# Crazebird-v0_8.net
KiCad netlist of a schematic drawn in EAGLE
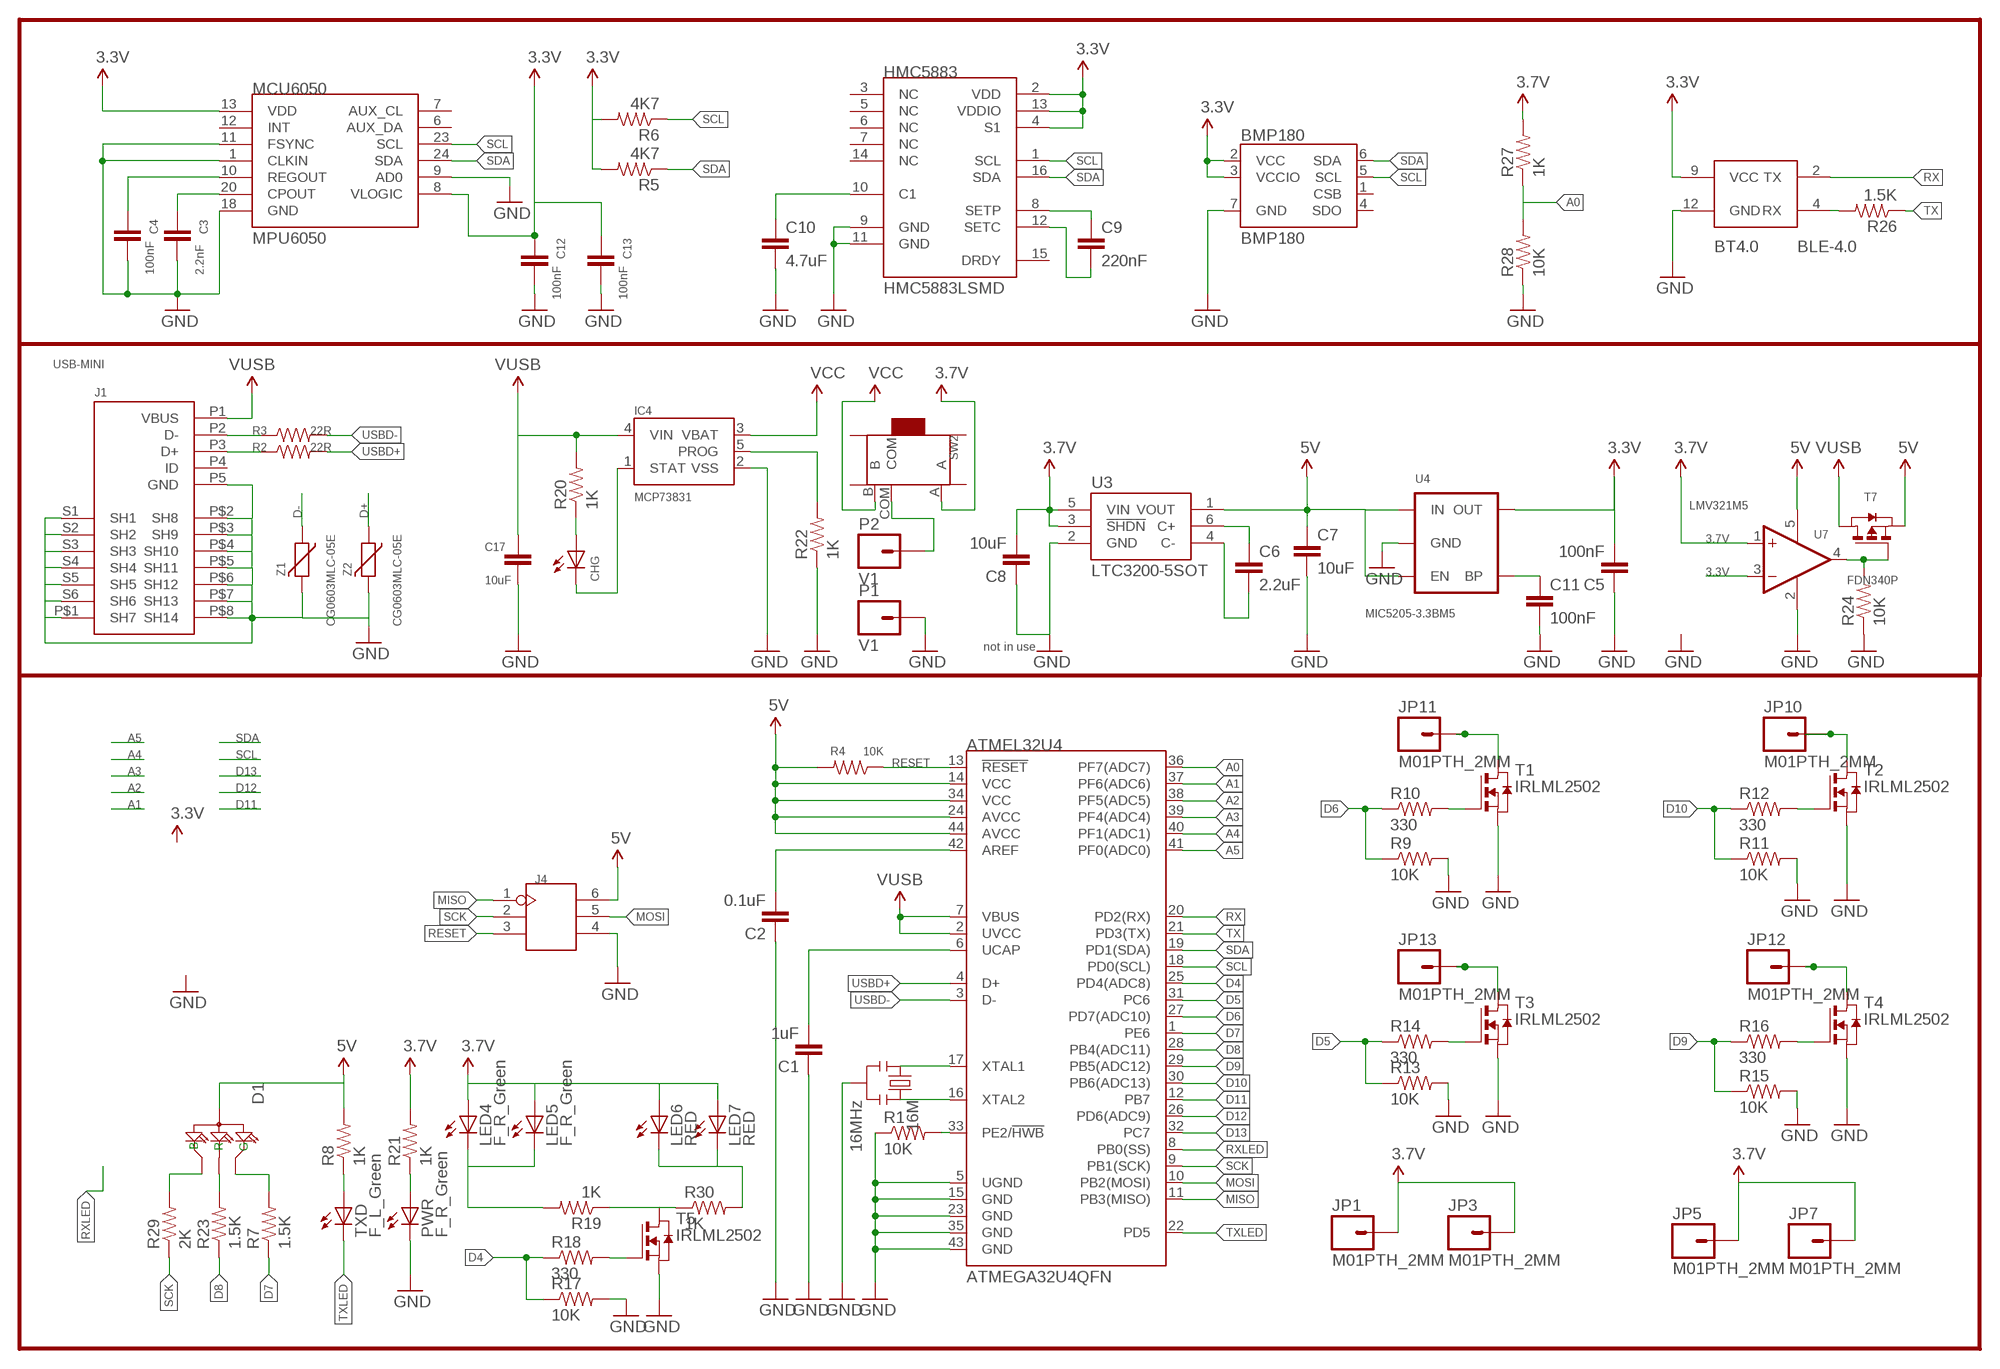
[diagram p0: schematic, sheet 1]

(export (version "E")
  (design (tool "Eeschema 10.0.6"))
  (components
    (comp (ref "16M")
      (value "16MHz")
      (footprint "eagle-import:RESONATOR-SMD")
      (libsource (lib "eagle-import") (part "RESONATOR16MHZ"))
    )
    (comp (ref "ATMEL32U4")
      (value "ATMEGA32U4QFN")
      (footprint "eagle-import:SPARKFUN-DIGITALIC_QFN-44")
      (libsource (lib "eagle-import") (part "ATMEGA32U4QFN"))
    )
    (comp (ref "BMP180")
      (value "BMP180")
      (footprint "eagle-import:BMP180")
      (libsource (lib "eagle-import") (part "BMP180"))
    )
    (comp (ref "BT4.0")
      (value "BLE-4.0")
      (footprint "eagle-import:HEXAIRBOT-HEXNANO_BLUETOOTH_HM11")
      (libsource (lib "eagle-import") (part "HEXAIRBOT-HEXNANO_BLUETOOTH_HM11"))
    )
    (comp (ref "C1")
      (value "1uF")
      (footprint "eagle-import:0402-CAP")
      (libsource (lib "eagle-import") (part "SparkFun-Passives_CAP0402-CAP"))
    )
    (comp (ref "C2")
      (value "0.1uF")
      (footprint "eagle-import:0402-CAP")
      (libsource (lib "eagle-import") (part "SparkFun-Passives_CAP0402-CAP"))
    )
    (comp (ref "C3")
      (value "2.2nF")
      (footprint "eagle-import:0402-CAP")
      (libsource (lib "eagle-import") (part "SparkFun-Passives_CAP0402-CAP"))
    )
    (comp (ref "C4")
      (value "100nF")
      (footprint "eagle-import:0402-CAP")
      (libsource (lib "eagle-import") (part "SparkFun-Passives_CAP0402-CAP"))
    )
    (comp (ref "C5")
      (value "100nF")
      (footprint "eagle-import:0402-CAP")
      (libsource (lib "eagle-import") (part "SparkFun-Passives_CAP0402-CAP"))
    )
    (comp (ref "C6")
      (value "2.2uF")
      (footprint "eagle-import:0402-CAP")
      (libsource (lib "eagle-import") (part "SparkFun-Passives_CAP0402-CAP"))
    )
    (comp (ref "C7")
      (value "10uF")
      (footprint "eagle-import:0402-CAP")
      (libsource (lib "eagle-import") (part "SparkFun-Passives_CAP0402-CAP"))
    )
    (comp (ref "C8")
      (value "10uF")
      (footprint "eagle-import:0805")
      (libsource (lib "eagle-import") (part "SparkFun-Passives_CAP0805"))
    )
    (comp (ref "C9")
      (value "220nF")
      (footprint "eagle-import:0402-CAP")
      (libsource (lib "eagle-import") (part "SparkFun-Passives_CAP0402-CAP"))
    )
    (comp (ref "C10")
      (value "4.7uF")
      (footprint "eagle-import:0402-CAP")
      (libsource (lib "eagle-import") (part "SparkFun-Passives_CAP0402-CAP"))
    )
    (comp (ref "C11")
      (value "100nF")
      (footprint "eagle-import:0402-CAP")
      (libsource (lib "eagle-import") (part "SparkFun-Passives_CAP0402-CAP"))
    )
    (comp (ref "C12")
      (value "100nF")
      (footprint "eagle-import:0402-CAP")
      (libsource (lib "eagle-import") (part "SparkFun-Passives_CAP0402-CAP"))
    )
    (comp (ref "C13")
      (value "100nF")
      (footprint "eagle-import:0402-CAP")
      (libsource (lib "eagle-import") (part "SparkFun-Passives_CAP0402-CAP"))
    )
    (comp (ref "C17")
      (value "10uF")
      (footprint "eagle-import:0805")
      (libsource (lib "eagle-import") (part "CAP0805"))
    )
    (comp (ref "CHG")
      (value "Yellow")
      (footprint "eagle-import:CHIPLED_0603")
      (libsource (lib "eagle-import") (part "LEDCHIPLED_0603"))
    )
    (comp (ref "D1")
      (value "LED-ARGB-4P-1206")
      (footprint "eagle-import:LED-4P-1206-3.0X1.5")
      (libsource (lib "eagle-import") (part "LED-ARGB-4P-1206"))
    )
    (comp (ref "HMC5883")
      (value "HMC5883LSMD")
      (footprint "eagle-import:16LPCC")
      (libsource (lib "eagle-import") (part "HMC5883LSMD"))
    )
    (comp (ref "IC4")
      (value "MCP73831")
      (footprint "eagle-import:SOT23-5")
      (libsource (lib "eagle-import") (part "MCP73831"))
    )
    (comp (ref "J1")
      (value "USB-MINI")
      (footprint "eagle-import:USB_MICRO")
      (libsource (lib "eagle-import") (part "USB-MINI"))
    )
    (comp (ref "J4")
      (value "CONNECTOR_HEADER-2X3P-2.0")
      (footprint "eagle-import:CONNECTOR_2X3P-2.0")
      (libsource (lib "eagle-import") (part "CONNECTOR_HEADER-2X3P-2.0"))
    )
    (comp (ref "JP1")
      (value "M01PTH_2MM")
      (footprint "eagle-import:1X01_2MM")
      (libsource (lib "eagle-import") (part "duinofun-connector_M01PTH_2MM"))
    )
    (comp (ref "JP3")
      (value "M01PTH_2MM")
      (footprint "eagle-import:1X01_2MM")
      (libsource (lib "eagle-import") (part "duinofun-connector_M01PTH_2MM"))
    )
    (comp (ref "JP5")
      (value "M01PTH_2MM")
      (footprint "eagle-import:1X01_2MM")
      (libsource (lib "eagle-import") (part "duinofun-connector_M01PTH_2MM"))
    )
    (comp (ref "JP7")
      (value "M01PTH_2MM")
      (footprint "eagle-import:1X01_2MM")
      (libsource (lib "eagle-import") (part "duinofun-connector_M01PTH_2MM"))
    )
    (comp (ref "JP10")
      (value "M01PTH_2MM")
      (footprint "eagle-import:1X01_2MM")
      (libsource (lib "eagle-import") (part "duinofun-connector_M01PTH_2MM"))
    )
    (comp (ref "JP11")
      (value "M01PTH_2MM")
      (footprint "eagle-import:1X01_2MM")
      (libsource (lib "eagle-import") (part "duinofun-connector_M01PTH_2MM"))
    )
    (comp (ref "JP12")
      (value "M01PTH_2MM")
      (footprint "eagle-import:1X01_2MM")
      (libsource (lib "eagle-import") (part "duinofun-connector_M01PTH_2MM"))
    )
    (comp (ref "JP13")
      (value "M01PTH_2MM")
      (footprint "eagle-import:1X01_2MM")
      (libsource (lib "eagle-import") (part "duinofun-connector_M01PTH_2MM"))
    )
    (comp (ref "LED4")
      (value "F_R_Green")
      (footprint "eagle-import:CHIPLED_0603")
      (libsource (lib "eagle-import") (part "LEDCHIPLED_0603"))
    )
    (comp (ref "LED5")
      (value "F_R_Green")
      (footprint "eagle-import:CHIPLED_0603")
      (libsource (lib "eagle-import") (part "LEDCHIPLED_0603"))
    )
    (comp (ref "LED6")
      (value "RED")
      (footprint "eagle-import:CHIPLED_0603")
      (libsource (lib "eagle-import") (part "LEDCHIPLED_0603"))
    )
    (comp (ref "LED7")
      (value "RED")
      (footprint "eagle-import:CHIPLED_0603")
      (libsource (lib "eagle-import") (part "LEDCHIPLED_0603"))
    )
    (comp (ref "MCU6050")
      (value "MPU6050")
      (footprint "eagle-import:TESTING_QFN-24-4MM2")
      (libsource (lib "eagle-import") (part "TESTING_MPU-6050-1"))
    )
    (comp (ref "P1")
      (value "V1")
      (footprint "eagle-import:1X01")
      (libsource (lib "eagle-import") (part "M01PTH"))
    )
    (comp (ref "P2")
      (value "V1")
      (footprint "eagle-import:1X01")
      (libsource (lib "eagle-import") (part "M01PTH"))
    )
    (comp (ref "PWR")
      (value "F_R_Green")
      (footprint "eagle-import:CHIPLED_0603")
      (libsource (lib "eagle-import") (part "LEDCHIPLED_0603"))
    )
    (comp (ref "R1")
      (value "10K")
      (footprint "eagle-import:0402-RES")
      (libsource (lib "eagle-import") (part "RESISTOR0402-RES"))
    )
    (comp (ref "R2")
      (value "22R")
      (footprint "eagle-import:0402-RES")
      (libsource (lib "eagle-import") (part "RESISTOR0402-RES"))
    )
    (comp (ref "R3")
      (value "22R")
      (footprint "eagle-import:0402-RES")
      (libsource (lib "eagle-import") (part "RESISTOR0402-RES"))
    )
    (comp (ref "R4")
      (value "10K")
      (footprint "eagle-import:0402-RES")
      (libsource (lib "eagle-import") (part "RESISTOR0402-RES"))
    )
    (comp (ref "R5")
      (value "4K7")
      (footprint "eagle-import:0402-RES")
      (libsource (lib "eagle-import") (part "RESISTOR0402-RES"))
    )
    (comp (ref "R6")
      (value "4K7")
      (footprint "eagle-import:0402-RES")
      (libsource (lib "eagle-import") (part "RESISTOR0402-RES"))
    )
    (comp (ref "R7")
      (value "1.5K")
      (footprint "eagle-import:0402-RES")
      (libsource (lib "eagle-import") (part "RESISTOR0402-RES"))
    )
    (comp (ref "R8")
      (value "1K")
      (footprint "eagle-import:0402-RES")
      (libsource (lib "eagle-import") (part "RESISTOR0402-RES"))
    )
    (comp (ref "R9")
      (value "10K")
      (footprint "eagle-import:0402-RES")
      (libsource (lib "eagle-import") (part "RESISTOR0402-RES"))
    )
    (comp (ref "R10")
      (value "330")
      (footprint "eagle-import:0402-RES")
      (libsource (lib "eagle-import") (part "RESISTOR0402-RES"))
    )
    (comp (ref "R11")
      (value "10K")
      (footprint "eagle-import:0402-RES")
      (libsource (lib "eagle-import") (part "RESISTOR0402-RES"))
    )
    (comp (ref "R12")
      (value "330")
      (footprint "eagle-import:0402-RES")
      (libsource (lib "eagle-import") (part "RESISTOR0402-RES"))
    )
    (comp (ref "R13")
      (value "10K")
      (footprint "eagle-import:0402-RES")
      (libsource (lib "eagle-import") (part "RESISTOR0402-RES"))
    )
    (comp (ref "R14")
      (value "330")
      (footprint "eagle-import:0402-RES")
      (libsource (lib "eagle-import") (part "RESISTOR0402-RES"))
    )
    (comp (ref "R15")
      (value "10K")
      (footprint "eagle-import:0402-RES")
      (libsource (lib "eagle-import") (part "RESISTOR0402-RES"))
    )
    (comp (ref "R16")
      (value "330")
      (footprint "eagle-import:0402-RES")
      (libsource (lib "eagle-import") (part "RESISTOR0402-RES"))
    )
    (comp (ref "R17")
      (value "10K")
      (footprint "eagle-import:0402-RES")
      (libsource (lib "eagle-import") (part "RESISTOR0402-RES"))
    )
    (comp (ref "R18")
      (value "330")
      (footprint "eagle-import:0402-RES")
      (libsource (lib "eagle-import") (part "RESISTOR0402-RES"))
    )
    (comp (ref "R19")
      (value "1K")
      (footprint "eagle-import:0402-RES")
      (libsource (lib "eagle-import") (part "RESISTOR0402-RES"))
    )
    (comp (ref "R20")
      (value "1K")
      (footprint "eagle-import:0402-RES")
      (libsource (lib "eagle-import") (part "RESISTOR0402-RES"))
    )
    (comp (ref "R21")
      (value "1K")
      (footprint "eagle-import:0402-RES")
      (libsource (lib "eagle-import") (part "RESISTOR0402-RES"))
    )
    (comp (ref "R22")
      (value "1K")
      (footprint "eagle-import:0402-RES")
      (libsource (lib "eagle-import") (part "RESISTOR0402-RES"))
    )
    (comp (ref "R23")
      (value "1.5K")
      (footprint "eagle-import:0402-RES")
      (libsource (lib "eagle-import") (part "RESISTOR0402-RES"))
    )
    (comp (ref "R24")
      (value "10K")
      (footprint "eagle-import:0402-RES")
      (libsource (lib "eagle-import") (part "RESISTOR0402-RES"))
    )
    (comp (ref "R26")
      (value "1.5K")
      (footprint "eagle-import:0402-RES")
      (libsource (lib "eagle-import") (part "RESISTOR0402-RES"))
    )
    (comp (ref "R27")
      (value "1K")
      (footprint "eagle-import:0402-RES")
      (libsource (lib "eagle-import") (part "RESISTOR0402-RES"))
    )
    (comp (ref "R28")
      (value "10K")
      (footprint "eagle-import:0402-RES")
      (libsource (lib "eagle-import") (part "RESISTOR0402-RES"))
    )
    (comp (ref "R29")
      (value "2K")
      (footprint "eagle-import:0402-RES")
      (libsource (lib "eagle-import") (part "RESISTOR0402-RES"))
    )
    (comp (ref "R30")
      (value "1K")
      (footprint "eagle-import:0402-RES")
      (libsource (lib "eagle-import") (part "RESISTOR0402-RES"))
    )
    (comp (ref "SW2")
      (value "SWITCH-3P-SMD-6.6X2.8")
      (footprint "eagle-import:3P-SMD-2CH-6.6X2.8-REINFORCE")
      (libsource (lib "eagle-import") (part "SWITCH-3P-SMD-6.6X2.8"))
    )
    (comp (ref "T1")
      (value "IRLML2502")
      (footprint "eagle-import:SOT-23")
      (libsource (lib "eagle-import") (part "NMOSSOT23"))
    )
    (comp (ref "T2")
      (value "IRLML2502")
      (footprint "eagle-import:SOT-23")
      (libsource (lib "eagle-import") (part "NMOSSOT23"))
    )
    (comp (ref "T3")
      (value "IRLML2502")
      (footprint "eagle-import:SOT-23")
      (libsource (lib "eagle-import") (part "NMOSSOT23"))
    )
    (comp (ref "T4")
      (value "IRLML2502")
      (footprint "eagle-import:SOT-23")
      (libsource (lib "eagle-import") (part "NMOSSOT23"))
    )
    (comp (ref "T5")
      (value "IRLML2502")
      (footprint "eagle-import:SOT-23")
      (libsource (lib "eagle-import") (part "NMOSSOT23"))
    )
    (comp (ref "T7")
      (value "FDN340P")
      (footprint "eagle-import:SOT23")
      (libsource (lib "eagle-import") (part "FDN340P"))
    )
    (comp (ref "TXD")
      (value "F_L_Green")
      (footprint "eagle-import:CHIPLED_0603")
      (libsource (lib "eagle-import") (part "LEDCHIPLED_0603"))
    )
    (comp (ref "U3")
      (value "LTC3200-5SOT")
      (footprint "eagle-import:SOT23-6")
      (libsource (lib "eagle-import") (part "LTC3200-5SOT"))
    )
    (comp (ref "U4")
      (value "MIC5205-3.3BM5")
      (footprint "eagle-import:SOT23-5")
      (libsource (lib "eagle-import") (part "MIC52053.3V"))
    )
    (comp (ref "U7")
      (value "LMV321M5")
      (footprint "eagle-import:SOT23-5")
      (libsource (lib "eagle-import") (part "LMV321?M5"))
    )
    (comp (ref "Z1")
      (value "CG0603MLC-05E")
      (footprint "eagle-import:CT_CN0603")
      (libsource (lib "eagle-import") (part "VARISTORCN0603"))
    )
    (comp (ref "Z2")
      (value "CG0603MLC-05E")
      (footprint "eagle-import:CT_CN0603")
      (libsource (lib "eagle-import") (part "VARISTORCN0603"))
    )
  )
  (nets
    (net (code "1") (name "/D+") (class "Default")
      (node (ref "J1") (pin "P3") (pinfunction "D+_P3") (pintype "bidirectional"))
      (node (ref "R2") (pin "1") (pinfunction "1_1") (pintype "passive"))
      (node (ref "Z2") (pin "1") (pinfunction "1_1") (pintype "passive"))
    )
    (net (code "2") (name "/D-") (class "Default")
      (node (ref "J1") (pin "P2") (pinfunction "D-_P2") (pintype "bidirectional"))
      (node (ref "R3") (pin "1") (pinfunction "1_1") (pintype "passive"))
      (node (ref "Z1") (pin "1") (pinfunction "1_1") (pintype "passive"))
    )
    (net (code "3") (name "3.3V") (class "Default")
      (node (ref "BMP180") (pin "2") (pinfunction "VCC_2") (pintype "power_in"))
      (node (ref "BMP180") (pin "3") (pinfunction "VCCIO_3") (pintype "power_in"))
      (node (ref "BT4.0") (pin "9") (pinfunction "VCC_9") (pintype "bidirectional"))
      (node (ref "C12") (pin "1") (pinfunction "1_1") (pintype "passive"))
      (node (ref "C13") (pin "1") (pinfunction "1_1") (pintype "passive"))
      (node (ref "C5") (pin "2") (pinfunction "2_2") (pintype "passive"))
      (node (ref "HMC5883") (pin "13") (pinfunction "VDDIO_13") (pintype "bidirectional"))
      (node (ref "HMC5883") (pin "2") (pinfunction "VDD_2") (pintype "bidirectional"))
      (node (ref "HMC5883") (pin "4") (pinfunction "S1_4") (pintype "bidirectional"))
      (node (ref "MCU6050") (pin "13") (pinfunction "VDD_13") (pintype "bidirectional"))
      (node (ref "MCU6050") (pin "8") (pinfunction "VLOGIC_8") (pintype "bidirectional"))
      (node (ref "R5") (pin "2") (pinfunction "2_2") (pintype "passive"))
      (node (ref "R6") (pin "2") (pinfunction "2_2") (pintype "passive"))
      (node (ref "U4") (pin "5") (pinfunction "OUT_5") (pintype "passive"))
      (node (ref "U7") (pin "3") (pinfunction "-IN_3") (pintype "input"))
    )
    (net (code "4") (name "3.7V") (class "Default")
      (node (ref "C8") (pin "2") (pinfunction "2_2") (pintype "passive"))
      (node (ref "JP1") (pin "1") (pinfunction "1_1") (pintype "passive"))
      (node (ref "JP3") (pin "1") (pinfunction "1_1") (pintype "passive"))
      (node (ref "JP5") (pin "1") (pinfunction "1_1") (pintype "passive"))
      (node (ref "JP7") (pin "1") (pinfunction "1_1") (pintype "passive"))
      (node (ref "LED4") (pin "A") (pinfunction "A_A") (pintype "passive"))
      (node (ref "LED5") (pin "A") (pinfunction "A_A") (pintype "passive"))
      (node (ref "LED6") (pin "A") (pinfunction "A_A") (pintype "passive"))
      (node (ref "LED7") (pin "A") (pinfunction "A_A") (pintype "passive"))
      (node (ref "R21") (pin "2") (pinfunction "2_2") (pintype "passive"))
      (node (ref "R27") (pin "2") (pinfunction "2_2") (pintype "passive"))
      (node (ref "SW2") (pin "A") (pinfunction "A_A") (pintype "bidirectional"))
      (node (ref "U3") (pin "3") (pinfunction "~{SHDN}_3") (pintype "bidirectional"))
      (node (ref "U3") (pin "5") (pinfunction "VIN_5") (pintype "bidirectional"))
      (node (ref "U7") (pin "1") (pinfunction "+IN_1") (pintype "input"))
    )
    (net (code "5") (name "5V") (class "Default")
      (node (ref "ATMEL32U4") (pin "14") (pinfunction "VCC_14") (pintype "bidirectional"))
      (node (ref "ATMEL32U4") (pin "24") (pinfunction "AVCC_24") (pintype "bidirectional"))
      (node (ref "ATMEL32U4") (pin "34") (pinfunction "VCC_34") (pintype "bidirectional"))
      (node (ref "ATMEL32U4") (pin "44") (pinfunction "AVCC_44") (pintype "bidirectional"))
      (node (ref "C7") (pin "1") (pinfunction "1_1") (pintype "passive"))
      (node (ref "D1") (pin "2") (pinfunction "+_2") (pintype "bidirectional"))
      (node (ref "J4") (pin "6") (pinfunction "6_6") (pintype "bidirectional"))
      (node (ref "R4") (pin "2") (pinfunction "2_2") (pintype "passive"))
      (node (ref "R8") (pin "2") (pinfunction "2_2") (pintype "passive"))
      (node (ref "T7") (pin "2") (pinfunction "S_2") (pintype "passive"))
      (node (ref "U3") (pin "1") (pinfunction "VOUT_1") (pintype "bidirectional"))
      (node (ref "U4") (pin "1") (pinfunction "IN_1") (pintype "input"))
      (node (ref "U4") (pin "3") (pinfunction "EN_3") (pintype "input"))
      (node (ref "U7") (pin "5") (pinfunction "V+_5") (pintype "power_in"))
    )
    (net (code "6") (name "A0") (class "Default")
      (node (ref "ATMEL32U4") (pin "36") (pinfunction "PF7(ADC7)_36") (pintype "bidirectional"))
      (node (ref "R27") (pin "1") (pinfunction "1_1") (pintype "passive"))
      (node (ref "R28") (pin "2") (pinfunction "2_2") (pintype "passive"))
    )
    (net (code "7") (name "A1") (class "Default")
      (node (ref "ATMEL32U4") (pin "37") (pinfunction "PF6(ADC6)_37") (pintype "bidirectional"))
    )
    (net (code "8") (name "A2") (class "Default")
      (node (ref "ATMEL32U4") (pin "38") (pinfunction "PF5(ADC5)_38") (pintype "bidirectional"))
    )
    (net (code "9") (name "A3") (class "Default")
      (node (ref "ATMEL32U4") (pin "39") (pinfunction "PF4(ADC4)_39") (pintype "bidirectional"))
    )
    (net (code "10") (name "A4") (class "Default")
      (node (ref "ATMEL32U4") (pin "40") (pinfunction "PF1(ADC1)_40") (pintype "bidirectional"))
    )
    (net (code "11") (name "A5") (class "Default")
      (node (ref "ATMEL32U4") (pin "41") (pinfunction "PF0(ADC0)_41") (pintype "bidirectional"))
    )
    (net (code "12") (name "D4") (class "Default")
      (node (ref "ATMEL32U4") (pin "25") (pinfunction "PD4(ADC8)_25") (pintype "bidirectional"))
      (node (ref "R17") (pin "1") (pinfunction "1_1") (pintype "passive"))
      (node (ref "R18") (pin "1") (pinfunction "1_1") (pintype "passive"))
    )
    (net (code "13") (name "D5") (class "Default")
      (node (ref "ATMEL32U4") (pin "31") (pinfunction "PC6_31") (pintype "bidirectional"))
      (node (ref "R13") (pin "1") (pinfunction "1_1") (pintype "passive"))
      (node (ref "R14") (pin "1") (pinfunction "1_1") (pintype "passive"))
    )
    (net (code "14") (name "D6") (class "Default")
      (node (ref "ATMEL32U4") (pin "27") (pinfunction "PD7(ADC10)_27") (pintype "bidirectional"))
      (node (ref "R10") (pin "1") (pinfunction "1_1") (pintype "passive"))
      (node (ref "R9") (pin "1") (pinfunction "1_1") (pintype "passive"))
    )
    (net (code "15") (name "D7") (class "Default")
      (node (ref "ATMEL32U4") (pin "1") (pinfunction "PE6_1") (pintype "bidirectional"))
      (node (ref "R7") (pin "1") (pinfunction "1_1") (pintype "passive"))
    )
    (net (code "16") (name "D8") (class "Default")
      (node (ref "ATMEL32U4") (pin "28") (pinfunction "PB4(ADC11)_28") (pintype "bidirectional"))
      (node (ref "R23") (pin "1") (pinfunction "1_1") (pintype "passive"))
    )
    (net (code "17") (name "D9") (class "Default")
      (node (ref "ATMEL32U4") (pin "29") (pinfunction "PB5(ADC12)_29") (pintype "bidirectional"))
      (node (ref "R15") (pin "1") (pinfunction "1_1") (pintype "passive"))
      (node (ref "R16") (pin "1") (pinfunction "1_1") (pintype "passive"))
    )
    (net (code "18") (name "D10") (class "Default")
      (node (ref "ATMEL32U4") (pin "30") (pinfunction "PB6(ADC13)_30") (pintype "bidirectional"))
      (node (ref "R11") (pin "1") (pinfunction "1_1") (pintype "passive"))
      (node (ref "R12") (pin "1") (pinfunction "1_1") (pintype "passive"))
    )
    (net (code "19") (name "D11") (class "Default")
      (node (ref "ATMEL32U4") (pin "12") (pinfunction "PB7_12") (pintype "bidirectional"))
    )
    (net (code "20") (name "D12") (class "Default")
      (node (ref "ATMEL32U4") (pin "26") (pinfunction "PD6(ADC9)_26") (pintype "bidirectional"))
    )
    (net (code "21") (name "D13") (class "Default")
      (node (ref "ATMEL32U4") (pin "32") (pinfunction "PC7_32") (pintype "bidirectional"))
    )
    (net (code "22") (name "GND") (class "Default")
      (node (ref "16M") (pin "2") (pinfunction "2_2") (pintype "passive"))
      (node (ref "ATMEL32U4") (pin "15") (pinfunction "GND_15") (pintype "bidirectional"))
      (node (ref "ATMEL32U4") (pin "23") (pinfunction "GND_23") (pintype "bidirectional"))
      (node (ref "ATMEL32U4") (pin "35") (pinfunction "GND_35") (pintype "bidirectional"))
      (node (ref "ATMEL32U4") (pin "43") (pinfunction "GND_43") (pintype "bidirectional"))
      (node (ref "ATMEL32U4") (pin "5") (pinfunction "UGND_5") (pintype "bidirectional"))
      (node (ref "BMP180") (pin "7") (pinfunction "GND_7") (pintype "power_in"))
      (node (ref "BT4.0") (pin "12") (pinfunction "GND_12") (pintype "bidirectional"))
      (node (ref "C1") (pin "1") (pinfunction "1_1") (pintype "passive"))
      (node (ref "C10") (pin "2") (pinfunction "2_2") (pintype "passive"))
      (node (ref "C11") (pin "2") (pinfunction "2_2") (pintype "passive"))
      (node (ref "C12") (pin "2") (pinfunction "2_2") (pintype "passive"))
      (node (ref "C13") (pin "2") (pinfunction "2_2") (pintype "passive"))
      (node (ref "C17") (pin "1") (pinfunction "1_1") (pintype "passive"))
      (node (ref "C2") (pin "1") (pinfunction "1_1") (pintype "passive"))
      (node (ref "C3") (pin "2") (pinfunction "2_2") (pintype "passive"))
      (node (ref "C4") (pin "2") (pinfunction "2_2") (pintype "passive"))
      (node (ref "C5") (pin "1") (pinfunction "1_1") (pintype "passive"))
      (node (ref "C7") (pin "2") (pinfunction "2_2") (pintype "passive"))
      (node (ref "C8") (pin "1") (pinfunction "1_1") (pintype "passive"))
      (node (ref "HMC5883") (pin "11") (pinfunction "GND_11") (pintype "bidirectional"))
      (node (ref "HMC5883") (pin "9") (pinfunction "GND_9") (pintype "bidirectional"))
      (node (ref "IC4") (pin "2") (pinfunction "VSS_2") (pintype "power_in"))
      (node (ref "J1") (pin "P$1") (pinfunction "SH7_P$1") (pintype "passive"))
      (node (ref "J1") (pin "P$2") (pinfunction "SH8_P$2") (pintype "passive"))
      (node (ref "J1") (pin "P$3") (pinfunction "SH9_P$3") (pintype "passive"))
      (node (ref "J1") (pin "P$4") (pinfunction "SH10_P$4") (pintype "passive"))
      (node (ref "J1") (pin "P$5") (pinfunction "SH11_P$5") (pintype "passive"))
      (node (ref "J1") (pin "P$6") (pinfunction "SH12_P$6") (pintype "passive"))
      (node (ref "J1") (pin "P$7") (pinfunction "SH13_P$7") (pintype "passive"))
      (node (ref "J1") (pin "P$8") (pinfunction "SH14_P$8") (pintype "passive"))
      (node (ref "J1") (pin "P5") (pinfunction "GND_P5") (pintype "passive"))
      (node (ref "J1") (pin "S1") (pinfunction "SH1_S1") (pintype "passive"))
      (node (ref "J1") (pin "S2") (pinfunction "SH2_S2") (pintype "passive"))
      (node (ref "J1") (pin "S3") (pinfunction "SH3_S3") (pintype "passive"))
      (node (ref "J1") (pin "S4") (pinfunction "SH4_S4") (pintype "passive"))
      (node (ref "J1") (pin "S5") (pinfunction "SH5_S5") (pintype "passive"))
      (node (ref "J1") (pin "S6") (pinfunction "SH6_S6") (pintype "passive"))
      (node (ref "J4") (pin "4") (pinfunction "4_4") (pintype "bidirectional"))
      (node (ref "MCU6050") (pin "1") (pinfunction "CLKIN_1") (pintype "bidirectional"))
      (node (ref "MCU6050") (pin "11") (pinfunction "FSYNC_11") (pintype "bidirectional"))
      (node (ref "MCU6050") (pin "18") (pinfunction "GND_18") (pintype "bidirectional"))
      (node (ref "MCU6050") (pin "9") (pinfunction "AD0_9") (pintype "bidirectional"))
      (node (ref "P1") (pin "1") (pinfunction "1_1") (pintype "passive"))
      (node (ref "PWR") (pin "C") (pinfunction "C_C") (pintype "passive"))
      (node (ref "R1") (pin "1") (pinfunction "1_1") (pintype "passive"))
      (node (ref "R11") (pin "2") (pinfunction "2_2") (pintype "passive"))
      (node (ref "R13") (pin "2") (pinfunction "2_2") (pintype "passive"))
      (node (ref "R15") (pin "2") (pinfunction "2_2") (pintype "passive"))
      (node (ref "R17") (pin "2") (pinfunction "2_2") (pintype "passive"))
      (node (ref "R22") (pin "1") (pinfunction "1_1") (pintype "passive"))
      (node (ref "R24") (pin "1") (pinfunction "1_1") (pintype "passive"))
      (node (ref "R28") (pin "1") (pinfunction "1_1") (pintype "passive"))
      (node (ref "R9") (pin "2") (pinfunction "2_2") (pintype "passive"))
      (node (ref "T1") (pin "2") (pinfunction "S_2") (pintype "passive"))
      (node (ref "T2") (pin "2") (pinfunction "S_2") (pintype "passive"))
      (node (ref "T3") (pin "2") (pinfunction "S_2") (pintype "passive"))
      (node (ref "T4") (pin "2") (pinfunction "S_2") (pintype "passive"))
      (node (ref "T5") (pin "2") (pinfunction "S_2") (pintype "passive"))
      (node (ref "U3") (pin "2") (pinfunction "GND_2") (pintype "bidirectional"))
      (node (ref "U4") (pin "2") (pinfunction "GND_2") (pintype "input"))
      (node (ref "U7") (pin "2") (pinfunction "V-_2") (pintype "power_in"))
      (node (ref "Z1") (pin "2") (pinfunction "2_2") (pintype "passive"))
      (node (ref "Z2") (pin "2") (pinfunction "2_2") (pintype "passive"))
    )
    (net (code "23") (name "MISO") (class "Default")
      (node (ref "ATMEL32U4") (pin "11") (pinfunction "PB3(MISO)_11") (pintype "bidirectional"))
      (node (ref "J4") (pin "1") (pinfunction "1_1") (pintype "bidirectional"))
    )
    (net (code "24") (name "MOSI") (class "Default")
      (node (ref "ATMEL32U4") (pin "10") (pinfunction "PB2(MOSI)_10") (pintype "bidirectional"))
      (node (ref "J4") (pin "5") (pinfunction "5_5") (pintype "bidirectional"))
    )
    (net (code "25") (name "Net-(ATMEL32U4-AREF)") (class "Default")
      (node (ref "ATMEL32U4") (pin "42") (pinfunction "AREF_42") (pintype "bidirectional"))
      (node (ref "C2") (pin "2") (pinfunction "2_2") (pintype "passive"))
    )
    (net (code "26") (name "Net-(ATMEL32U4-PE2{slash}~{HWB})") (class "Default")
      (node (ref "ATMEL32U4") (pin "33") (pinfunction "PE2/~{HWB}_33") (pintype "bidirectional"))
      (node (ref "R1") (pin "2") (pinfunction "2_2") (pintype "passive"))
    )
    (net (code "27") (name "Net-(ATMEL32U4-UCAP)") (class "Default")
      (node (ref "ATMEL32U4") (pin "6") (pinfunction "UCAP_6") (pintype "bidirectional"))
      (node (ref "C1") (pin "2") (pinfunction "2_2") (pintype "passive"))
    )
    (net (code "28") (name "Net-(ATMEL32U4-XTAL1)") (class "Default")
      (node (ref "16M") (pin "1") (pinfunction "1_1") (pintype "passive"))
      (node (ref "ATMEL32U4") (pin "17") (pinfunction "XTAL1_17") (pintype "bidirectional"))
    )
    (net (code "29") (name "Net-(ATMEL32U4-XTAL2)") (class "Default")
      (node (ref "16M") (pin "3") (pinfunction "3_3") (pintype "passive"))
      (node (ref "ATMEL32U4") (pin "16") (pinfunction "XTAL2_16") (pintype "bidirectional"))
    )
    (net (code "30") (name "Net-(BT4.0-RX)") (class "Default")
      (node (ref "BT4.0") (pin "4") (pinfunction "RX_4") (pintype "bidirectional"))
      (node (ref "R26") (pin "2") (pinfunction "2_2") (pintype "passive"))
    )
    (net (code "31") (name "Net-(CHG-PadA)") (class "Default")
      (node (ref "CHG") (pin "A") (pinfunction "A_A") (pintype "passive"))
      (node (ref "R20") (pin "1") (pinfunction "1_1") (pintype "passive"))
    )
    (net (code "32") (name "Net-(D1-B)") (class "Default")
      (node (ref "D1") (pin "1") (pinfunction "B_1") (pintype "bidirectional"))
      (node (ref "R29") (pin "2") (pinfunction "2_2") (pintype "passive"))
    )
    (net (code "33") (name "Net-(D1-G)") (class "Default")
      (node (ref "D1") (pin "3") (pinfunction "G_3") (pintype "bidirectional"))
      (node (ref "R7") (pin "2") (pinfunction "2_2") (pintype "passive"))
    )
    (net (code "34") (name "Net-(D1-R)") (class "Default")
      (node (ref "D1") (pin "4") (pinfunction "R_4") (pintype "bidirectional"))
      (node (ref "R23") (pin "2") (pinfunction "2_2") (pintype "passive"))
    )
    (net (code "35") (name "Net-(HMC5883-C1)") (class "Default")
      (node (ref "C10") (pin "1") (pinfunction "1_1") (pintype "passive"))
      (node (ref "HMC5883") (pin "10") (pinfunction "C1_10") (pintype "bidirectional"))
    )
    (net (code "36") (name "Net-(HMC5883-SETC)") (class "Default")
      (node (ref "C9") (pin "2") (pinfunction "2_2") (pintype "passive"))
      (node (ref "HMC5883") (pin "12") (pinfunction "SETC_12") (pintype "bidirectional"))
    )
    (net (code "37") (name "Net-(HMC5883-SETP)") (class "Default")
      (node (ref "C9") (pin "1") (pinfunction "1_1") (pintype "passive"))
      (node (ref "HMC5883") (pin "8") (pinfunction "SETP_8") (pintype "bidirectional"))
    )
    (net (code "38") (name "Net-(IC4-PROG)") (class "Default")
      (node (ref "IC4") (pin "5") (pinfunction "PROG_5") (pintype "input"))
      (node (ref "R22") (pin "2") (pinfunction "2_2") (pintype "passive"))
    )
    (net (code "39") (name "Net-(IC4-STAT)") (class "Default")
      (node (ref "CHG") (pin "C") (pinfunction "C_C") (pintype "passive"))
      (node (ref "IC4") (pin "1") (pinfunction "STAT_1") (pintype "output"))
    )
    (net (code "40") (name "Net-(LED4-PadC)") (class "Default")
      (node (ref "LED4") (pin "C") (pinfunction "C_C") (pintype "passive"))
      (node (ref "LED5") (pin "C") (pinfunction "C_C") (pintype "passive"))
      (node (ref "R19") (pin "2") (pinfunction "2_2") (pintype "passive"))
    )
    (net (code "41") (name "Net-(LED6-PadC)") (class "Default")
      (node (ref "LED6") (pin "C") (pinfunction "C_C") (pintype "passive"))
      (node (ref "LED7") (pin "C") (pinfunction "C_C") (pintype "passive"))
      (node (ref "R30") (pin "2") (pinfunction "2_2") (pintype "passive"))
    )
    (net (code "42") (name "Net-(MCU6050-CPOUT)") (class "Default")
      (node (ref "C3") (pin "1") (pinfunction "1_1") (pintype "passive"))
      (node (ref "MCU6050") (pin "20") (pinfunction "CPOUT_20") (pintype "bidirectional"))
    )
    (net (code "43") (name "Net-(MCU6050-REGOUT)") (class "Default")
      (node (ref "C4") (pin "1") (pinfunction "1_1") (pintype "passive"))
      (node (ref "MCU6050") (pin "10") (pinfunction "REGOUT_10") (pintype "bidirectional"))
    )
    (net (code "44") (name "Net-(P2-Pad1)") (class "Default")
      (node (ref "P2") (pin "1") (pinfunction "1_1") (pintype "passive"))
      (node (ref "SW2") (pin "COM") (pinfunction "COM_COM") (pintype "bidirectional"))
    )
    (net (code "45") (name "Net-(PWR-PadA)") (class "Default")
      (node (ref "PWR") (pin "A") (pinfunction "A_A") (pintype "passive"))
      (node (ref "R21") (pin "1") (pinfunction "1_1") (pintype "passive"))
    )
    (net (code "46") (name "Net-(R8-Pad1)") (class "Default")
      (node (ref "R8") (pin "1") (pinfunction "1_1") (pintype "passive"))
      (node (ref "TXD") (pin "A") (pinfunction "A_A") (pintype "passive"))
    )
    (net (code "47") (name "Net-(T1-D)") (class "Default")
      (node (ref "JP11") (pin "1") (pinfunction "1_1") (pintype "passive"))
      (node (ref "T1") (pin "1") (pinfunction "D_1") (pintype "passive"))
    )
    (net (code "48") (name "Net-(T1-G)") (class "Default")
      (node (ref "R10") (pin "2") (pinfunction "2_2") (pintype "passive"))
      (node (ref "T1") (pin "3") (pinfunction "G_3") (pintype "passive"))
    )
    (net (code "49") (name "Net-(T2-D)") (class "Default")
      (node (ref "JP10") (pin "1") (pinfunction "1_1") (pintype "passive"))
      (node (ref "T2") (pin "1") (pinfunction "D_1") (pintype "passive"))
    )
    (net (code "50") (name "Net-(T2-G)") (class "Default")
      (node (ref "R12") (pin "2") (pinfunction "2_2") (pintype "passive"))
      (node (ref "T2") (pin "3") (pinfunction "G_3") (pintype "passive"))
    )
    (net (code "51") (name "Net-(T3-D)") (class "Default")
      (node (ref "JP13") (pin "1") (pinfunction "1_1") (pintype "passive"))
      (node (ref "T3") (pin "1") (pinfunction "D_1") (pintype "passive"))
    )
    (net (code "52") (name "Net-(T3-G)") (class "Default")
      (node (ref "R14") (pin "2") (pinfunction "2_2") (pintype "passive"))
      (node (ref "T3") (pin "3") (pinfunction "G_3") (pintype "passive"))
    )
    (net (code "53") (name "Net-(T4-D)") (class "Default")
      (node (ref "JP12") (pin "1") (pinfunction "1_1") (pintype "passive"))
      (node (ref "T4") (pin "1") (pinfunction "D_1") (pintype "passive"))
    )
    (net (code "54") (name "Net-(T4-G)") (class "Default")
      (node (ref "R16") (pin "2") (pinfunction "2_2") (pintype "passive"))
      (node (ref "T4") (pin "3") (pinfunction "G_3") (pintype "passive"))
    )
    (net (code "55") (name "Net-(T5-D)") (class "Default")
      (node (ref "R19") (pin "1") (pinfunction "1_1") (pintype "passive"))
      (node (ref "R30") (pin "1") (pinfunction "1_1") (pintype "passive"))
      (node (ref "T5") (pin "1") (pinfunction "D_1") (pintype "passive"))
    )
    (net (code "56") (name "Net-(T5-G)") (class "Default")
      (node (ref "R18") (pin "2") (pinfunction "2_2") (pintype "passive"))
      (node (ref "T5") (pin "3") (pinfunction "G_3") (pintype "passive"))
    )
    (net (code "57") (name "Net-(T7-G)") (class "Default")
      (node (ref "R24") (pin "2") (pinfunction "2_2") (pintype "passive"))
      (node (ref "T7") (pin "3") (pinfunction "G_3") (pintype "passive"))
      (node (ref "U7") (pin "4") (pinfunction "OUT_4") (pintype "output"))
    )
    (net (code "58") (name "Net-(U3-C+)") (class "Default")
      (node (ref "C6") (pin "1") (pinfunction "1_1") (pintype "passive"))
      (node (ref "U3") (pin "6") (pinfunction "C+_6") (pintype "bidirectional"))
    )
    (net (code "59") (name "Net-(U3-C-)") (class "Default")
      (node (ref "C6") (pin "2") (pinfunction "2_2") (pintype "passive"))
      (node (ref "U3") (pin "4") (pinfunction "C-_4") (pintype "bidirectional"))
    )
    (net (code "60") (name "Net-(U4-BP)") (class "Default")
      (node (ref "C11") (pin "1") (pinfunction "1_1") (pintype "passive"))
      (node (ref "U4") (pin "4") (pinfunction "BP_4") (pintype "input"))
    )
    (net (code "61") (name "RESET") (class "Default")
      (node (ref "ATMEL32U4") (pin "13") (pinfunction "~{RESET}_13") (pintype "bidirectional"))
      (node (ref "J4") (pin "3") (pinfunction "3_3") (pintype "bidirectional"))
      (node (ref "R4") (pin "1") (pinfunction "1_1") (pintype "passive"))
    )
    (net (code "62") (name "RX") (class "Default")
      (node (ref "ATMEL32U4") (pin "20") (pinfunction "PD2(RX)_20") (pintype "bidirectional"))
      (node (ref "BT4.0") (pin "2") (pinfunction "TX_2") (pintype "bidirectional"))
    )
    (net (code "63") (name "RXLED") (class "Default")
      (node (ref "ATMEL32U4") (pin "8") (pinfunction "PB0(SS)_8") (pintype "bidirectional"))
    )
    (net (code "64") (name "SCK") (class "Default")
      (node (ref "ATMEL32U4") (pin "9") (pinfunction "PB1(SCK)_9") (pintype "bidirectional"))
      (node (ref "J4") (pin "2") (pinfunction "2_2") (pintype "bidirectional"))
      (node (ref "R29") (pin "1") (pinfunction "1_1") (pintype "passive"))
    )
    (net (code "65") (name "SCL") (class "Default")
      (node (ref "ATMEL32U4") (pin "18") (pinfunction "PD0(SCL)_18") (pintype "bidirectional"))
      (node (ref "BMP180") (pin "5") (pinfunction "SCL_5") (pintype "input"))
      (node (ref "HMC5883") (pin "1") (pinfunction "SCL_1") (pintype "bidirectional"))
      (node (ref "MCU6050") (pin "23") (pinfunction "SCL_23") (pintype "bidirectional"))
      (node (ref "R6") (pin "1") (pinfunction "1_1") (pintype "passive"))
    )
    (net (code "66") (name "SDA") (class "Default")
      (node (ref "ATMEL32U4") (pin "19") (pinfunction "PD1(SDA)_19") (pintype "bidirectional"))
      (node (ref "BMP180") (pin "6") (pinfunction "SDA_6") (pintype "bidirectional"))
      (node (ref "HMC5883") (pin "16") (pinfunction "SDA_16") (pintype "bidirectional"))
      (node (ref "MCU6050") (pin "24") (pinfunction "SDA_24") (pintype "bidirectional"))
      (node (ref "R5") (pin "1") (pinfunction "1_1") (pintype "passive"))
    )
    (net (code "67") (name "TX") (class "Default")
      (node (ref "ATMEL32U4") (pin "21") (pinfunction "PD3(TX)_21") (pintype "bidirectional"))
      (node (ref "R26") (pin "1") (pinfunction "1_1") (pintype "passive"))
    )
    (net (code "68") (name "TXLED") (class "Default")
      (node (ref "ATMEL32U4") (pin "22") (pinfunction "PD5_22") (pintype "bidirectional"))
      (node (ref "TXD") (pin "C") (pinfunction "C_C") (pintype "passive"))
    )
    (net (code "69") (name "USBD+") (class "Default")
      (node (ref "ATMEL32U4") (pin "4") (pinfunction "D+_4") (pintype "bidirectional"))
      (node (ref "R2") (pin "2") (pinfunction "2_2") (pintype "passive"))
    )
    (net (code "70") (name "USBD-") (class "Default")
      (node (ref "ATMEL32U4") (pin "3") (pinfunction "D-_3") (pintype "bidirectional"))
      (node (ref "R3") (pin "2") (pinfunction "2_2") (pintype "passive"))
    )
    (net (code "71") (name "VCC") (class "Default")
      (node (ref "IC4") (pin "3") (pinfunction "VBAT_3") (pintype "power_in"))
      (node (ref "SW2") (pin "B") (pinfunction "B_B") (pintype "bidirectional"))
    )
    (net (code "72") (name "VUSB") (class "Default")
      (node (ref "ATMEL32U4") (pin "2") (pinfunction "UVCC_2") (pintype "bidirectional"))
      (node (ref "ATMEL32U4") (pin "7") (pinfunction "VBUS_7") (pintype "bidirectional"))
      (node (ref "C17") (pin "2") (pinfunction "2_2") (pintype "passive"))
      (node (ref "IC4") (pin "4") (pinfunction "VIN_4") (pintype "power_in"))
      (node (ref "J1") (pin "P1") (pinfunction "VBUS_P1") (pintype "power_in"))
      (node (ref "R20") (pin "2") (pinfunction "2_2") (pintype "passive"))
      (node (ref "T7") (pin "1") (pinfunction "D_1") (pintype "passive"))
    )
    (net (code "73") (name "unconnected-(BMP180-CSB-Pad1)") (class "Default")
      (node (ref "BMP180") (pin "1") (pinfunction "CSB_1") (pintype "output"))
    )
    (net (code "74") (name "unconnected-(BMP180-SDO-Pad4)") (class "Default")
      (node (ref "BMP180") (pin "4") (pinfunction "SDO_4") (pintype "input"))
    )
    (net (code "75") (name "unconnected-(HMC5883-DRDY-Pad15)") (class "Default")
      (node (ref "HMC5883") (pin "15") (pinfunction "DRDY_15") (pintype "bidirectional"))
    )
    (net (code "76") (name "unconnected-(HMC5883-NC-Pad3)") (class "Default")
      (node (ref "HMC5883") (pin "3") (pinfunction "NC_3") (pintype "bidirectional"))
    )
    (net (code "77") (name "unconnected-(HMC5883-NC-Pad5)") (class "Default")
      (node (ref "HMC5883") (pin "5") (pinfunction "NC_5") (pintype "bidirectional"))
    )
    (net (code "78") (name "unconnected-(HMC5883-NC-Pad6)") (class "Default")
      (node (ref "HMC5883") (pin "6") (pinfunction "NC_6") (pintype "bidirectional"))
    )
    (net (code "79") (name "unconnected-(HMC5883-NC-Pad7)") (class "Default")
      (node (ref "HMC5883") (pin "7") (pinfunction "NC_7") (pintype "bidirectional"))
    )
    (net (code "80") (name "unconnected-(HMC5883-NC-Pad14)") (class "Default")
      (node (ref "HMC5883") (pin "14") (pinfunction "NC_14") (pintype "bidirectional"))
    )
    (net (code "81") (name "unconnected-(J1-ID-PadP4)") (class "Default")
      (node (ref "J1") (pin "P4") (pinfunction "ID_P4") (pintype "bidirectional"))
    )
    (net (code "82") (name "unconnected-(MCU6050-AUX_CL-Pad7)") (class "Default")
      (node (ref "MCU6050") (pin "7") (pinfunction "AUX_CL_7") (pintype "bidirectional"))
    )
    (net (code "83") (name "unconnected-(MCU6050-AUX_DA-Pad6)") (class "Default")
      (node (ref "MCU6050") (pin "6") (pinfunction "AUX_DA_6") (pintype "bidirectional"))
    )
    (net (code "84") (name "unconnected-(MCU6050-INT-Pad12)") (class "Default")
      (node (ref "MCU6050") (pin "12") (pinfunction "INT_12") (pintype "bidirectional"))
    )
    (net (code "85") (name "unconnected-(SW2-PadSS1)") (class "Default")
      (node (ref "SW2") (pin "SS1") (pinfunction "SS1_SS1") (pintype "bidirectional"))
    )
    (net (code "86") (name "unconnected-(SW2-PadSS2)") (class "Default")
      (node (ref "SW2") (pin "SS2") (pinfunction "SS2_SS2") (pintype "bidirectional"))
    )
    (net (code "87") (name "unconnected-(SW2-PadSS3)") (class "Default")
      (node (ref "SW2") (pin "SS3") (pinfunction "SS3_SS3") (pintype "bidirectional"))
    )
    (net (code "88") (name "unconnected-(SW2-PadSS4)") (class "Default")
      (node (ref "SW2") (pin "SS4") (pinfunction "SS4_SS4") (pintype "bidirectional"))
    )
  )
)
